# UWB.net
KiCad netlist of a schematic drawn in Altium Designer
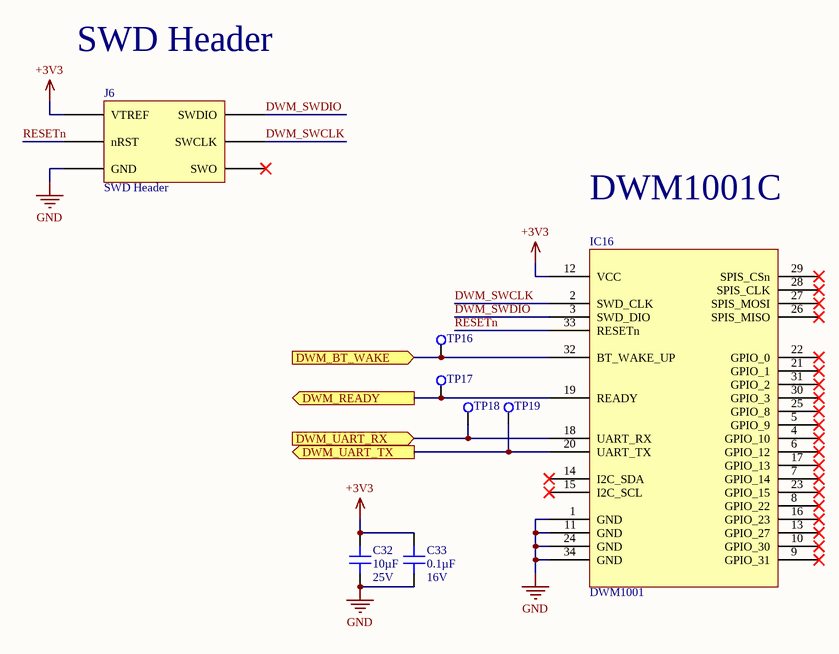
[diagram p0: UWB.SchDoc]

(export (version "E")
  (design (tool "Eeschema 10.0.6"))
  (components
    (comp (ref "C32")
      (value "10µF")
      (footprint "CAP 0603_1608")
      (description "CAP CER 10UF 25V X5R 0603")
      (fields
        (field (name "PART NUMBER") "CC0603MRX5R8BB106")
        (field (name "MANUFACTURER") "Yageo")
        (field (name "VOLTAGE - RATED") "25V")
      )
      (libsource (lib "Celestial Altium Library - altium_library") (part "Capacitor"))
    )
    (comp (ref "C33")
      (value "0.1µF")
      (footprint "CAP 0603_1608")
      (description "CAP CER 0.1UF 16V X7R 0603")
      (fields
        (field (name "PART NUMBER") "CC0603KRX7R7BB104")
        (field (name "MANUFACTURER") "Yageo")
        (field (name "VOLTAGE - RATED") "16V")
      )
      (libsource (lib "Celestial Altium Library - altium_library") (part "Capacitor"))
    )
    (comp (ref "IC16")
      (value "DWM1001")
      (footprint "DWM1001")
      (description "RF TXRX MODULE UWB/BLUETOOTH RTL")
      (fields (field (name "MANUFACTURER") "DecaWave"))
      (libsource (lib "Drone") (part "DWM1001"))
    )
    (comp (ref "J6")
      (value "SWD Header")
      (footprint "SWD Header")
      (libsource (lib "Drone") (part "SWD Header"))
    )
    (comp (ref "TP16")
      (value "TestPoint")
      (footprint "TestPoint")
      (libsource (lib "Drone") (part "TestPoint"))
    )
    (comp (ref "TP17")
      (value "TestPoint")
      (footprint "TestPoint")
      (libsource (lib "Drone") (part "TestPoint"))
    )
    (comp (ref "TP18")
      (value "TestPoint")
      (footprint "TestPoint")
      (libsource (lib "Drone") (part "TestPoint"))
    )
    (comp (ref "TP19")
      (value "TestPoint")
      (footprint "TestPoint")
      (libsource (lib "Drone") (part "TestPoint"))
    )
  )
  (nets
    (net (code "1") (name "+3V3") (class "Default")
      (node (ref "C32") (pin "2") (pinfunction "2_2") (pintype "passive"))
      (node (ref "C33") (pin "2") (pinfunction "2_2") (pintype "passive"))
      (node (ref "IC16") (pin "12") (pinfunction "VCC_12") (pintype "passive"))
      (node (ref "J6") (pin "VTREF") (pinfunction "VTREF_VTREF") (pintype "passive"))
    )
    (net (code "2") (name "/DWM_BT_WAKE") (class "Default")
      (node (ref "IC16") (pin "32") (pinfunction "BT_WAKE_UP_32") (pintype "passive"))
      (node (ref "TP16") (pin "1") (pinfunction "1_1") (pintype "passive"))
    )
    (net (code "3") (name "/DWM_READY") (class "Default")
      (node (ref "IC16") (pin "19") (pinfunction "READY_19") (pintype "passive"))
      (node (ref "TP17") (pin "1") (pinfunction "1_1") (pintype "passive"))
    )
    (net (code "4") (name "/DWM_SWCLK") (class "Default")
      (node (ref "IC16") (pin "2") (pinfunction "SWD_CLK_2") (pintype "passive"))
      (node (ref "J6") (pin "SWCLK") (pinfunction "SWCLK_SWCLK") (pintype "passive"))
    )
    (net (code "5") (name "/DWM_SWDIO") (class "Default")
      (node (ref "IC16") (pin "3") (pinfunction "SWD_DIO_3") (pintype "passive"))
      (node (ref "J6") (pin "SWDIO") (pinfunction "SWDIO_SWDIO") (pintype "passive"))
    )
    (net (code "6") (name "/DWM_UART_RX") (class "Default")
      (node (ref "IC16") (pin "18") (pinfunction "UART_RX_18") (pintype "passive"))
      (node (ref "TP18") (pin "1") (pinfunction "1_1") (pintype "passive"))
    )
    (net (code "7") (name "/DWM_UART_TX") (class "Default")
      (node (ref "IC16") (pin "20") (pinfunction "UART_TX_20") (pintype "passive"))
      (node (ref "TP19") (pin "1") (pinfunction "1_1") (pintype "passive"))
    )
    (net (code "8") (name "/RESETn") (class "Default")
      (node (ref "IC16") (pin "33") (pinfunction "RESETn_33") (pintype "passive"))
      (node (ref "J6") (pin "nRST") (pinfunction "nRST_nRST") (pintype "passive"))
    )
    (net (code "9") (name "GND") (class "Default")
      (node (ref "C32") (pin "1") (pinfunction "1_1") (pintype "passive"))
      (node (ref "C33") (pin "1") (pinfunction "1_1") (pintype "passive"))
      (node (ref "IC16") (pin "1") (pinfunction "GND_1") (pintype "passive"))
      (node (ref "IC16") (pin "11") (pinfunction "GND_11") (pintype "passive"))
      (node (ref "IC16") (pin "24") (pinfunction "GND_24") (pintype "passive"))
      (node (ref "IC16") (pin "34") (pinfunction "GND_34") (pintype "passive"))
      (node (ref "J6") (pin "GND") (pinfunction "GND_GND") (pintype "passive"))
    )
    (net (code "10") (name "unconnected-(IC16-GPIO_0-Pad22)") (class "Default")
      (node (ref "IC16") (pin "22") (pinfunction "GPIO_0_22") (pintype "passive+no_connect"))
    )
    (net (code "11") (name "unconnected-(IC16-GPIO_1-Pad21)") (class "Default")
      (node (ref "IC16") (pin "21") (pinfunction "GPIO_1_21") (pintype "passive+no_connect"))
    )
    (net (code "12") (name "unconnected-(IC16-GPIO_2-Pad31)") (class "Default")
      (node (ref "IC16") (pin "31") (pinfunction "GPIO_2_31") (pintype "passive+no_connect"))
    )
    (net (code "13") (name "unconnected-(IC16-GPIO_3-Pad30)") (class "Default")
      (node (ref "IC16") (pin "30") (pinfunction "GPIO_3_30") (pintype "passive+no_connect"))
    )
    (net (code "14") (name "unconnected-(IC16-GPIO_8-Pad25)") (class "Default")
      (node (ref "IC16") (pin "25") (pinfunction "GPIO_8_25") (pintype "passive+no_connect"))
    )
    (net (code "15") (name "unconnected-(IC16-GPIO_9-Pad5)") (class "Default")
      (node (ref "IC16") (pin "5") (pinfunction "GPIO_9_5") (pintype "passive+no_connect"))
    )
    (net (code "16") (name "unconnected-(IC16-GPIO_10-Pad4)") (class "Default")
      (node (ref "IC16") (pin "4") (pinfunction "GPIO_10_4") (pintype "passive+no_connect"))
    )
    (net (code "17") (name "unconnected-(IC16-GPIO_12-Pad6)") (class "Default")
      (node (ref "IC16") (pin "6") (pinfunction "GPIO_12_6") (pintype "passive+no_connect"))
    )
    (net (code "18") (name "unconnected-(IC16-GPIO_13-Pad17)") (class "Default")
      (node (ref "IC16") (pin "17") (pinfunction "GPIO_13_17") (pintype "passive+no_connect"))
    )
    (net (code "19") (name "unconnected-(IC16-GPIO_14-Pad7)") (class "Default")
      (node (ref "IC16") (pin "7") (pinfunction "GPIO_14_7") (pintype "passive+no_connect"))
    )
    (net (code "20") (name "unconnected-(IC16-GPIO_15-Pad23)") (class "Default")
      (node (ref "IC16") (pin "23") (pinfunction "GPIO_15_23") (pintype "passive+no_connect"))
    )
    (net (code "21") (name "unconnected-(IC16-GPIO_22-Pad8)") (class "Default")
      (node (ref "IC16") (pin "8") (pinfunction "GPIO_22_8") (pintype "passive+no_connect"))
    )
    (net (code "22") (name "unconnected-(IC16-GPIO_23-Pad16)") (class "Default")
      (node (ref "IC16") (pin "16") (pinfunction "GPIO_23_16") (pintype "passive+no_connect"))
    )
    (net (code "23") (name "unconnected-(IC16-GPIO_27-Pad13)") (class "Default")
      (node (ref "IC16") (pin "13") (pinfunction "GPIO_27_13") (pintype "passive+no_connect"))
    )
    (net (code "24") (name "unconnected-(IC16-GPIO_30-Pad10)") (class "Default")
      (node (ref "IC16") (pin "10") (pinfunction "GPIO_30_10") (pintype "passive+no_connect"))
    )
    (net (code "25") (name "unconnected-(IC16-GPIO_31-Pad9)") (class "Default")
      (node (ref "IC16") (pin "9") (pinfunction "GPIO_31_9") (pintype "passive+no_connect"))
    )
    (net (code "26") (name "unconnected-(IC16-I2C_SCL-Pad15)") (class "Default")
      (node (ref "IC16") (pin "15") (pinfunction "I2C_SCL_15") (pintype "passive+no_connect"))
    )
    (net (code "27") (name "unconnected-(IC16-I2C_SDA-Pad14)") (class "Default")
      (node (ref "IC16") (pin "14") (pinfunction "I2C_SDA_14") (pintype "passive+no_connect"))
    )
    (net (code "28") (name "unconnected-(IC16-SPIS_CLK-Pad28)") (class "Default")
      (node (ref "IC16") (pin "28") (pinfunction "SPIS_CLK_28") (pintype "passive+no_connect"))
    )
    (net (code "29") (name "unconnected-(IC16-SPIS_CSn-Pad29)") (class "Default")
      (node (ref "IC16") (pin "29") (pinfunction "SPIS_CSn_29") (pintype "passive+no_connect"))
    )
    (net (code "30") (name "unconnected-(IC16-SPIS_MISO-Pad26)") (class "Default")
      (node (ref "IC16") (pin "26") (pinfunction "SPIS_MISO_26") (pintype "passive+no_connect"))
    )
    (net (code "31") (name "unconnected-(IC16-SPIS_MOSI-Pad27)") (class "Default")
      (node (ref "IC16") (pin "27") (pinfunction "SPIS_MOSI_27") (pintype "passive+no_connect"))
    )
    (net (code "32") (name "unconnected-(J6-PadSWO)") (class "Default")
      (node (ref "J6") (pin "SWO") (pinfunction "SWO_SWO") (pintype "passive+no_connect"))
    )
  )
)
